# HDMI1.net
KiCad netlist of a schematic drawn in Altium Designer
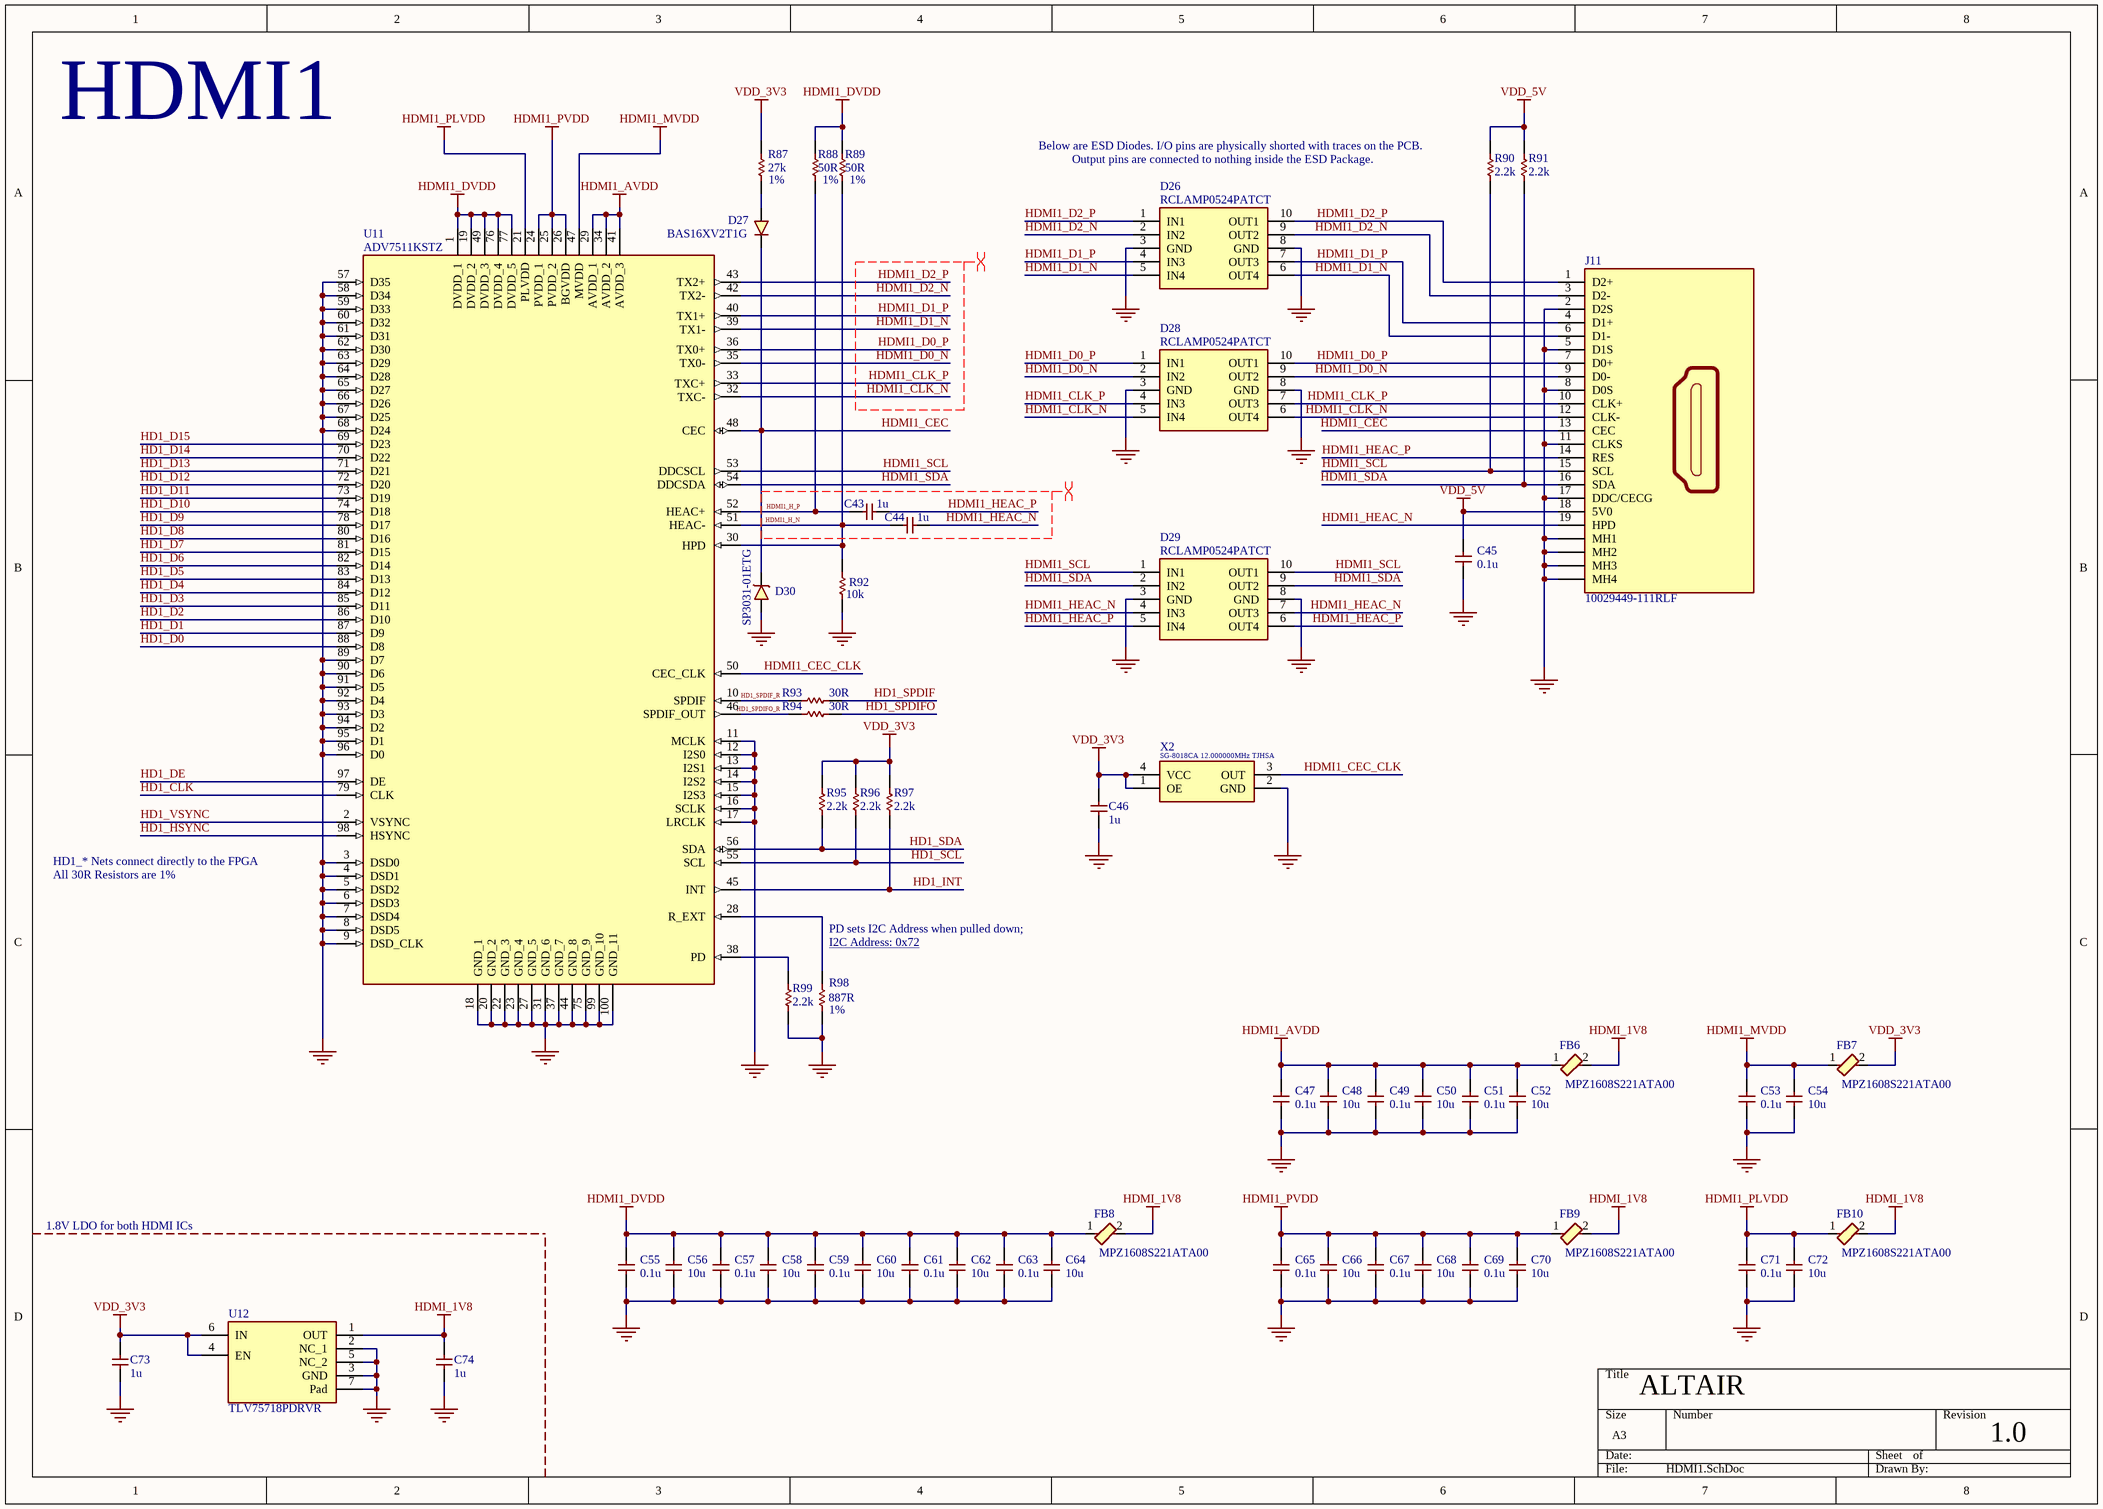
[diagram p0: HDMI1.SchDoc]

(export (version "E")
  (design (tool "Eeschema 10.0.6"))
  (components
    (comp (ref "C43")
      (value "1u")
      (footprint "CAP_0402")
      (description "Capacitor SMD 0402")
      (fields (field (name "JLCPCB PART #") "C14445") (field (name "PART NO") "CL05A105KP5NNNC"))
      (libsource (lib "personalGenericLib") (part "CAP_0402"))
    )
    (comp (ref "C44")
      (value "1u")
      (footprint "CAP_0402")
      (description "Capacitor SMD 0402")
      (fields (field (name "JLCPCB PART #") "C14445") (field (name "PART NO") "CL05A105KP5NNNC"))
      (libsource (lib "personalGenericLib") (part "CAP_0402"))
    )
    (comp (ref "C45")
      (value "0.1u")
      (footprint "CAP_0402")
      (description "Capacitor SMD 0402")
      (fields (field (name "PART NO") "CL05B104KO5NNNC") (field (name "JLCPCB PART #") "C338112"))
      (libsource (lib "personalGenericLib") (part "CAP_0402"))
    )
    (comp (ref "C46")
      (value "1u")
      (footprint "CAP_0402")
      (description "Capacitor SMD 0402")
      (fields (field (name "JLCPCB PART #") "C14445") (field (name "PART NO") "CL05A105KP5NNNC"))
      (libsource (lib "personalGenericLib") (part "CAP_0402"))
    )
    (comp (ref "C47")
      (value "0.1u")
      (footprint "CAP_0402")
      (description "Capacitor SMD 0402")
      (fields (field (name "PART NO") "CL05B104KO5NNNC") (field (name "JLCPCB PART #") "C338112"))
      (libsource (lib "personalGenericLib") (part "CAP_0402"))
    )
    (comp (ref "C48")
      (value "10u")
      (footprint "CAP_0402")
      (description "Capacitor SMD 0402")
      (fields (field (name "JLCPCB PART #") "C315248") (field (name "PART NO") "CL05A106MP5NUNC"))
      (libsource (lib "personalGenericLib") (part "CAP_0402"))
    )
    (comp (ref "C49")
      (value "0.1u")
      (footprint "CAP_0402")
      (description "Capacitor SMD 0402")
      (fields (field (name "PART NO") "CL05B104KO5NNNC") (field (name "JLCPCB PART #") "C338112"))
      (libsource (lib "personalGenericLib") (part "CAP_0402"))
    )
    (comp (ref "C50")
      (value "10u")
      (footprint "CAP_0402")
      (description "Capacitor SMD 0402")
      (fields (field (name "JLCPCB PART #") "C315248") (field (name "PART NO") "CL05A106MP5NUNC"))
      (libsource (lib "personalGenericLib") (part "CAP_0402"))
    )
    (comp (ref "C51")
      (value "0.1u")
      (footprint "CAP_0402")
      (description "Capacitor SMD 0402")
      (fields (field (name "PART NO") "CL05B104KO5NNNC") (field (name "JLCPCB PART #") "C338112"))
      (libsource (lib "personalGenericLib") (part "CAP_0402"))
    )
    (comp (ref "C52")
      (value "10u")
      (footprint "CAP_0402")
      (description "Capacitor SMD 0402")
      (fields (field (name "JLCPCB PART #") "C315248") (field (name "PART NO") "CL05A106MP5NUNC"))
      (libsource (lib "personalGenericLib") (part "CAP_0402"))
    )
    (comp (ref "C53")
      (value "0.1u")
      (footprint "CAP_0402")
      (description "Capacitor SMD 0402")
      (fields (field (name "PART NO") "CL05B104KO5NNNC") (field (name "JLCPCB PART #") "C338112"))
      (libsource (lib "personalGenericLib") (part "CAP_0402"))
    )
    (comp (ref "C54")
      (value "10u")
      (footprint "CAP_0402")
      (description "Capacitor SMD 0402")
      (fields (field (name "JLCPCB PART #") "C315248") (field (name "PART NO") "CL05A106MP5NUNC"))
      (libsource (lib "personalGenericLib") (part "CAP_0402"))
    )
    (comp (ref "C55")
      (value "0.1u")
      (footprint "CAP_0402")
      (description "Capacitor SMD 0402")
      (fields (field (name "PART NO") "CL05B104KO5NNNC") (field (name "JLCPCB PART #") "C338112"))
      (libsource (lib "personalGenericLib") (part "CAP_0402"))
    )
    (comp (ref "C56")
      (value "10u")
      (footprint "CAP_0402")
      (description "Capacitor SMD 0402")
      (fields (field (name "JLCPCB PART #") "C315248") (field (name "PART NO") "CL05A106MP5NUNC"))
      (libsource (lib "personalGenericLib") (part "CAP_0402"))
    )
    (comp (ref "C57")
      (value "0.1u")
      (footprint "CAP_0402")
      (description "Capacitor SMD 0402")
      (fields (field (name "PART NO") "CL05B104KO5NNNC") (field (name "JLCPCB PART #") "C338112"))
      (libsource (lib "personalGenericLib") (part "CAP_0402"))
    )
    (comp (ref "C58")
      (value "10u")
      (footprint "CAP_0402")
      (description "Capacitor SMD 0402")
      (fields (field (name "JLCPCB PART #") "C315248") (field (name "PART NO") "CL05A106MP5NUNC"))
      (libsource (lib "personalGenericLib") (part "CAP_0402"))
    )
    (comp (ref "C59")
      (value "0.1u")
      (footprint "CAP_0402")
      (description "Capacitor SMD 0402")
      (fields (field (name "PART NO") "CL05B104KO5NNNC") (field (name "JLCPCB PART #") "C338112"))
      (libsource (lib "personalGenericLib") (part "CAP_0402"))
    )
    (comp (ref "C60")
      (value "10u")
      (footprint "CAP_0402")
      (description "Capacitor SMD 0402")
      (fields (field (name "JLCPCB PART #") "C315248") (field (name "PART NO") "CL05A106MP5NUNC"))
      (libsource (lib "personalGenericLib") (part "CAP_0402"))
    )
    (comp (ref "C61")
      (value "0.1u")
      (footprint "CAP_0402")
      (description "Capacitor SMD 0402")
      (fields (field (name "PART NO") "CL05B104KO5NNNC") (field (name "JLCPCB PART #") "C338112"))
      (libsource (lib "personalGenericLib") (part "CAP_0402"))
    )
    (comp (ref "C62")
      (value "10u")
      (footprint "CAP_0402")
      (description "Capacitor SMD 0402")
      (fields (field (name "JLCPCB PART #") "C315248") (field (name "PART NO") "CL05A106MP5NUNC"))
      (libsource (lib "personalGenericLib") (part "CAP_0402"))
    )
    (comp (ref "C63")
      (value "0.1u")
      (footprint "CAP_0402")
      (description "Capacitor SMD 0402")
      (fields (field (name "PART NO") "CL05B104KO5NNNC") (field (name "JLCPCB PART #") "C338112"))
      (libsource (lib "personalGenericLib") (part "CAP_0402"))
    )
    (comp (ref "C64")
      (value "10u")
      (footprint "CAP_0402")
      (description "Capacitor SMD 0402")
      (fields (field (name "JLCPCB PART #") "C315248") (field (name "PART NO") "CL05A106MP5NUNC"))
      (libsource (lib "personalGenericLib") (part "CAP_0402"))
    )
    (comp (ref "C65")
      (value "0.1u")
      (footprint "CAP_0402")
      (description "Capacitor SMD 0402")
      (fields (field (name "PART NO") "CL05B104KO5NNNC") (field (name "JLCPCB PART #") "C338112"))
      (libsource (lib "personalGenericLib") (part "CAP_0402"))
    )
    (comp (ref "C66")
      (value "10u")
      (footprint "CAP_0402")
      (description "Capacitor SMD 0402")
      (fields (field (name "JLCPCB PART #") "C315248") (field (name "PART NO") "CL05A106MP5NUNC"))
      (libsource (lib "personalGenericLib") (part "CAP_0402"))
    )
    (comp (ref "C67")
      (value "0.1u")
      (footprint "CAP_0402")
      (description "Capacitor SMD 0402")
      (fields (field (name "PART NO") "CL05B104KO5NNNC") (field (name "JLCPCB PART #") "C338112"))
      (libsource (lib "personalGenericLib") (part "CAP_0402"))
    )
    (comp (ref "C68")
      (value "10u")
      (footprint "CAP_0402")
      (description "Capacitor SMD 0402")
      (fields (field (name "JLCPCB PART #") "C315248") (field (name "PART NO") "CL05A106MP5NUNC"))
      (libsource (lib "personalGenericLib") (part "CAP_0402"))
    )
    (comp (ref "C69")
      (value "0.1u")
      (footprint "CAP_0402")
      (description "Capacitor SMD 0402")
      (fields (field (name "PART NO") "CL05B104KO5NNNC") (field (name "JLCPCB PART #") "C338112"))
      (libsource (lib "personalGenericLib") (part "CAP_0402"))
    )
    (comp (ref "C70")
      (value "10u")
      (footprint "CAP_0402")
      (description "Capacitor SMD 0402")
      (fields (field (name "JLCPCB PART #") "C315248") (field (name "PART NO") "CL05A106MP5NUNC"))
      (libsource (lib "personalGenericLib") (part "CAP_0402"))
    )
    (comp (ref "C71")
      (value "0.1u")
      (footprint "CAP_0402")
      (description "Capacitor SMD 0402")
      (fields (field (name "PART NO") "CL05B104KO5NNNC") (field (name "JLCPCB PART #") "C338112"))
      (libsource (lib "personalGenericLib") (part "CAP_0402"))
    )
    (comp (ref "C72")
      (value "10u")
      (footprint "CAP_0402")
      (description "Capacitor SMD 0402")
      (fields (field (name "JLCPCB PART #") "C315248") (field (name "PART NO") "CL05A106MP5NUNC"))
      (libsource (lib "personalGenericLib") (part "CAP_0402"))
    )
    (comp (ref "C73")
      (value "1u")
      (footprint "CAP_0402")
      (description "Capacitor SMD 0402")
      (fields (field (name "JLCPCB PART #") "C14445") (field (name "PART NO") "CL05A105KP5NNNC"))
      (libsource (lib "personalGenericLib") (part "CAP_0402"))
    )
    (comp (ref "C74")
      (value "1u")
      (footprint "CAP_0402")
      (description "Capacitor SMD 0402")
      (fields (field (name "JLCPCB PART #") "C14445") (field (name "PART NO") "CL05A105KP5NNNC"))
      (libsource (lib "personalGenericLib") (part "CAP_0402"))
    )
    (comp (ref "D26")
      (value "RCLAMP0524PATCT")
      (footprint "RCLAMP0524PATCT")
      (description "TVS Diode (Uni-directional)")
      (fields (field (name "JLCPCB PART #") "C40960"))
      (libsource (lib "personalGenericLib") (part "RCLAMP0524PATCT"))
    )
    (comp (ref "D27")
      (value "BAS16XV2T1G")
      (footprint "SODFL1608X70N")
      (description "Diode (Switching)")
      (fields (field (name "JLCPCB PART #") "C152479"))
      (libsource (lib "personalGenericLib") (part "BAS16XV2T1G"))
    )
    (comp (ref "D28")
      (value "RCLAMP0524PATCT")
      (footprint "RCLAMP0524PATCT")
      (description "TVS Diode (Uni-directional)")
      (fields (field (name "JLCPCB PART #") "C40960"))
      (libsource (lib "personalGenericLib") (part "RCLAMP0524PATCT"))
    )
    (comp (ref "D29")
      (value "RCLAMP0524PATCT")
      (footprint "RCLAMP0524PATCT")
      (description "TVS Diode (Uni-directional)")
      (fields (field (name "JLCPCB PART #") "C40960"))
      (libsource (lib "personalGenericLib") (part "RCLAMP0524PATCT"))
    )
    (comp (ref "D30")
      (value "SP3031-01ETG")
      (footprint "SP303101ETG")
      (description "TVS Diode (Uni-directional)")
      (fields (field (name "JLCPCB PART #") "C207283"))
      (libsource (lib "personalGenericLib") (part "SP3031-01ETG"))
    )
    (comp (ref "FB6")
      (value "220")
      (footprint "BEADC1608X75N")
      (description "Ferrite Bead")
      (fields (field (name "PART NO") "MPZ1608S221ATA00") (field (name "JLCPCB PART #") "C76815"))
      (libsource (lib "personalGenericLib") (part "MPZ1608S221ATA00"))
    )
    (comp (ref "FB7")
      (value "220")
      (footprint "BEADC1608X75N")
      (description "Ferrite Bead")
      (fields (field (name "PART NO") "MPZ1608S221ATA00") (field (name "JLCPCB PART #") "C76815"))
      (libsource (lib "personalGenericLib") (part "MPZ1608S221ATA00"))
    )
    (comp (ref "FB8")
      (value "220")
      (footprint "BEADC1608X75N")
      (description "Ferrite Bead")
      (fields (field (name "PART NO") "MPZ1608S221ATA00") (field (name "JLCPCB PART #") "C76815"))
      (libsource (lib "personalGenericLib") (part "MPZ1608S221ATA00"))
    )
    (comp (ref "FB9")
      (value "220")
      (footprint "BEADC1608X75N")
      (description "Ferrite Bead")
      (fields (field (name "PART NO") "MPZ1608S221ATA00") (field (name "JLCPCB PART #") "C76815"))
      (libsource (lib "personalGenericLib") (part "MPZ1608S221ATA00"))
    )
    (comp (ref "FB10")
      (value "220")
      (footprint "BEADC1608X75N")
      (description "Ferrite Bead")
      (fields (field (name "PART NO") "MPZ1608S221ATA00") (field (name "JLCPCB PART #") "C76815"))
      (libsource (lib "personalGenericLib") (part "MPZ1608S221ATA00"))
    )
    (comp (ref "J11")
      (value "10029449-111RLF")
      (footprint "10029449111RLF")
      (description "HDMI Connector")
      (fields (field (name "JLCPCB PART #") "C427307"))
      (libsource (lib "personalGenericLib") (part "10029449-111RLF"))
    )
    (comp (ref "R87")
      (value "27k")
      (footprint "RES_0402")
      (description "Resistor SMD 0402")
      (fields
        (field (name "JLCPCB PART #") "C138022")
        (field (name "NOTE/MISC") "1%")
        (field (name "PART NO") "RC0402FR-0727KL")
      )
      (libsource (lib "personalGenericLib") (part "RES_0402"))
    )
    (comp (ref "R88")
      (value "50R")
      (footprint "RES_0402")
      (description "Resistor SMD 0402")
      (fields
        (field (name "JLCPCB PART #") "C853312")
        (field (name "NOTE/MISC") "1%")
        (field (name "PART NO") "RT0402BRE0750RL")
      )
      (libsource (lib "personalGenericLib") (part "RES_0402"))
    )
    (comp (ref "R89")
      (value "50R")
      (footprint "RES_0402")
      (description "Resistor SMD 0402")
      (fields
        (field (name "JLCPCB PART #") "C853312")
        (field (name "NOTE/MISC") "1%")
        (field (name "PART NO") "RT0402BRE0750RL")
      )
      (libsource (lib "personalGenericLib") (part "RES_0402"))
    )
    (comp (ref "R90")
      (value "2.2k")
      (footprint "RES_0402")
      (description "Resistor SMD 0402")
      (fields (field (name "JLCPCB PART #") "C163447") (field (name "PART NO") "RC0402JR-072K2L"))
      (libsource (lib "personalGenericLib") (part "RES_0402"))
    )
    (comp (ref "R91")
      (value "2.2k")
      (footprint "RES_0402")
      (description "Resistor SMD 0402")
      (fields (field (name "JLCPCB PART #") "C163447") (field (name "PART NO") "RC0402JR-072K2L"))
      (libsource (lib "personalGenericLib") (part "RES_0402"))
    )
    (comp (ref "R92")
      (value "10k")
      (footprint "RES_0402")
      (description "Resistor SMD 0402")
      (fields (field (name "JLCPCB PART #") "C60489") (field (name "PART NO") "RC0402JR-0710KL"))
      (libsource (lib "personalGenericLib") (part "RES_0402"))
    )
    (comp (ref "R93")
      (value "30R")
      (footprint "RES_0402")
      (description "Resistor SMD 0402")
      (fields (field (name "JLCPCB PART #") "C138007") (field (name "PART NO") "RC0402FR-0730RL"))
      (libsource (lib "personalGenericLib") (part "RES_0402"))
    )
    (comp (ref "R94")
      (value "30R")
      (footprint "RES_0402")
      (description "Resistor SMD 0402")
      (fields (field (name "JLCPCB PART #") "C138007") (field (name "PART NO") "RC0402FR-0730RL"))
      (libsource (lib "personalGenericLib") (part "RES_0402"))
    )
    (comp (ref "R95")
      (value "2.2k")
      (footprint "RES_0402")
      (description "Resistor SMD 0402")
      (fields (field (name "JLCPCB PART #") "C163447") (field (name "PART NO") "RC0402JR-072K2L"))
      (libsource (lib "personalGenericLib") (part "RES_0402"))
    )
    (comp (ref "R96")
      (value "2.2k")
      (footprint "RES_0402")
      (description "Resistor SMD 0402")
      (fields (field (name "JLCPCB PART #") "C163447") (field (name "PART NO") "RC0402JR-072K2L"))
      (libsource (lib "personalGenericLib") (part "RES_0402"))
    )
    (comp (ref "R97")
      (value "2.2k")
      (footprint "RES_0402")
      (description "Resistor SMD 0402")
      (fields (field (name "JLCPCB PART #") "C163447") (field (name "PART NO") "RC0402JR-072K2L"))
      (libsource (lib "personalGenericLib") (part "RES_0402"))
    )
    (comp (ref "R98")
      (value "887R")
      (footprint "RES_0402")
      (description "Resistor SMD 0402")
      (fields
        (field (name "JLCPCB PART #") "C4012675")
        (field (name "NOTE/MISC") "1%")
        (field (name "PART NO") "CRCW0402887RFKED")
      )
      (libsource (lib "personalGenericLib") (part "RES_0402"))
    )
    (comp (ref "R99")
      (value "2.2k")
      (footprint "RES_0402")
      (description "Resistor SMD 0402")
      (fields (field (name "JLCPCB PART #") "C163447") (field (name "PART NO") "RC0402JR-072K2L"))
      (libsource (lib "personalGenericLib") (part "RES_0402"))
    )
    (comp (ref "U11")
      (value "ADV7511KSTZ")
      (footprint "QFP50P1600X1600X160-100N")
      (description "HDMI RX IC")
      (fields (field (name "JLCPCB PART #") "C179459"))
      (libsource (lib "personalGenericLib") (part "ADV7511KSTZ"))
    )
    (comp (ref "U12")
      (value "TLV75718PDRVR")
      (footprint "SON65P200X200X80-7N")
      (description "LDO 1V8, 1V45-5V5 Input")
      (fields (field (name "JLCPCB PART #") "C2861386"))
      (libsource (lib "personalGenericLib") (part "TLV75718PDRVR"))
    )
    (comp (ref "X2")
      (value "SG-8018CA 12.000000MHz TJHSA")
      (footprint "SG8018CA147456MTJHPA3")
      (description "12 MHz Programmable Oscillator")
      (fields (field (name "JLCPCB PART #") "C390417"))
      (libsource (lib "personalGenericLib") (part "SG-8018CA 12.000000MHz TJHSA"))
    )
  )
  (nets
    (net (code "1") (name "/HD1_CLK") (class "Default")
      (node (ref "U11") (pin "79") (pinfunction "CLK_79") (pintype "input"))
    )
    (net (code "2") (name "/HD1_D0") (class "Default")
      (node (ref "U11") (pin "88") (pinfunction "D8_88") (pintype "input"))
    )
    (net (code "3") (name "/HD1_D1") (class "Default")
      (node (ref "U11") (pin "87") (pinfunction "D9_87") (pintype "input"))
    )
    (net (code "4") (name "/HD1_D2") (class "Default")
      (node (ref "U11") (pin "86") (pinfunction "D10_86") (pintype "input"))
    )
    (net (code "5") (name "/HD1_D3") (class "Default")
      (node (ref "U11") (pin "85") (pinfunction "D11_85") (pintype "input"))
    )
    (net (code "6") (name "/HD1_D4") (class "Default")
      (node (ref "U11") (pin "84") (pinfunction "D12_84") (pintype "input"))
    )
    (net (code "7") (name "/HD1_D5") (class "Default")
      (node (ref "U11") (pin "83") (pinfunction "D13_83") (pintype "input"))
    )
    (net (code "8") (name "/HD1_D6") (class "Default")
      (node (ref "U11") (pin "82") (pinfunction "D14_82") (pintype "input"))
    )
    (net (code "9") (name "/HD1_D7") (class "Default")
      (node (ref "U11") (pin "81") (pinfunction "D15_81") (pintype "input"))
    )
    (net (code "10") (name "/HD1_D8") (class "Default")
      (node (ref "U11") (pin "80") (pinfunction "D16_80") (pintype "input"))
    )
    (net (code "11") (name "/HD1_D9") (class "Default")
      (node (ref "U11") (pin "78") (pinfunction "D17_78") (pintype "input"))
    )
    (net (code "12") (name "/HD1_D10") (class "Default")
      (node (ref "U11") (pin "74") (pinfunction "D18_74") (pintype "input"))
    )
    (net (code "13") (name "/HD1_D11") (class "Default")
      (node (ref "U11") (pin "73") (pinfunction "D19_73") (pintype "input"))
    )
    (net (code "14") (name "/HD1_D12") (class "Default")
      (node (ref "U11") (pin "72") (pinfunction "D20_72") (pintype "input"))
    )
    (net (code "15") (name "/HD1_D13") (class "Default")
      (node (ref "U11") (pin "71") (pinfunction "D21_71") (pintype "input"))
    )
    (net (code "16") (name "/HD1_D14") (class "Default")
      (node (ref "U11") (pin "70") (pinfunction "D22_70") (pintype "input"))
    )
    (net (code "17") (name "/HD1_D15") (class "Default")
      (node (ref "U11") (pin "69") (pinfunction "D23_69") (pintype "input"))
    )
    (net (code "18") (name "/HD1_DE") (class "Default")
      (node (ref "U11") (pin "97") (pinfunction "DE_97") (pintype "input"))
    )
    (net (code "19") (name "/HD1_HSYNC") (class "Default")
      (node (ref "U11") (pin "98") (pinfunction "HSYNC_98") (pintype "input"))
    )
    (net (code "20") (name "/HD1_INT") (class "Default")
      (node (ref "R97") (pin "1") (pinfunction "1_1") (pintype "passive"))
      (node (ref "U11") (pin "45") (pinfunction "INT_45") (pintype "output"))
    )
    (net (code "21") (name "/HD1_SCL") (class "Default")
      (node (ref "R96") (pin "1") (pinfunction "1_1") (pintype "passive"))
      (node (ref "U11") (pin "55") (pinfunction "SCL_55") (pintype "input"))
    )
    (net (code "22") (name "/HD1_SDA") (class "Default")
      (node (ref "R95") (pin "1") (pinfunction "1_1") (pintype "passive"))
      (node (ref "U11") (pin "56") (pinfunction "SDA_56") (pintype "bidirectional"))
    )
    (net (code "23") (name "/HD1_SPDIF") (class "Default")
      (node (ref "R93") (pin "2") (pinfunction "2_2") (pintype "passive"))
    )
    (net (code "24") (name "/HD1_SPDIFO") (class "Default")
      (node (ref "R94") (pin "2") (pinfunction "2_2") (pintype "passive"))
    )
    (net (code "25") (name "/HD1_SPDIFO_R") (class "Default")
      (node (ref "R94") (pin "1") (pinfunction "1_1") (pintype "passive"))
      (node (ref "U11") (pin "46") (pinfunction "SPDIF_OUT_46") (pintype "output"))
    )
    (net (code "26") (name "/HD1_SPDIF_R") (class "Default")
      (node (ref "R93") (pin "1") (pinfunction "1_1") (pintype "passive"))
      (node (ref "U11") (pin "10") (pinfunction "SPDIF_10") (pintype "input"))
    )
    (net (code "27") (name "/HD1_VSYNC") (class "Default")
      (node (ref "U11") (pin "2") (pinfunction "VSYNC_2") (pintype "input"))
    )
    (net (code "28") (name "/HDMI1_CEC") (class "Default")
      (node (ref "D27") (pin "1") (pinfunction "K_1") (pintype "passive"))
      (node (ref "D30") (pin "1") (pinfunction "K_1") (pintype "passive"))
      (node (ref "J11") (pin "13") (pinfunction "CEC_13") (pintype "passive"))
      (node (ref "U11") (pin "48") (pinfunction "CEC_48") (pintype "bidirectional"))
    )
    (net (code "29") (name "/HDMI1_CEC_CLK") (class "Default")
      (node (ref "U11") (pin "50") (pinfunction "CEC_CLK_50") (pintype "input"))
      (node (ref "X2") (pin "3") (pinfunction "OUT_3") (pintype "passive"))
    )
    (net (code "30") (name "/HDMI1_CLK_N") (class "Default")
      (node (ref "D28") (pin "5") (pinfunction "IN4_5") (pintype "passive"))
      (node (ref "D28") (pin "6") (pinfunction "OUT4_6") (pintype "passive"))
      (node (ref "J11") (pin "12") (pinfunction "CLK-_12") (pintype "passive"))
      (node (ref "U11") (pin "32") (pinfunction "TXC-_32") (pintype "output"))
    )
    (net (code "31") (name "/HDMI1_CLK_P") (class "Default")
      (node (ref "D28") (pin "4") (pinfunction "IN3_4") (pintype "passive"))
      (node (ref "D28") (pin "7") (pinfunction "OUT3_7") (pintype "passive"))
      (node (ref "J11") (pin "10") (pinfunction "CLK+_10") (pintype "passive"))
      (node (ref "U11") (pin "33") (pinfunction "TXC+_33") (pintype "output"))
    )
    (net (code "32") (name "/HDMI1_D0_N") (class "Default")
      (node (ref "D28") (pin "2") (pinfunction "IN2_2") (pintype "passive"))
      (node (ref "D28") (pin "9") (pinfunction "OUT2_9") (pintype "passive"))
      (node (ref "J11") (pin "9") (pinfunction "D0-_9") (pintype "passive"))
      (node (ref "U11") (pin "35") (pinfunction "TX0-_35") (pintype "output"))
    )
    (net (code "33") (name "/HDMI1_D0_P") (class "Default")
      (node (ref "D28") (pin "1") (pinfunction "IN1_1") (pintype "passive"))
      (node (ref "D28") (pin "10") (pinfunction "OUT1_10") (pintype "passive"))
      (node (ref "J11") (pin "7") (pinfunction "D0+_7") (pintype "passive"))
      (node (ref "U11") (pin "36") (pinfunction "TX0+_36") (pintype "output"))
    )
    (net (code "34") (name "/HDMI1_D1_N") (class "Default")
      (node (ref "D26") (pin "5") (pinfunction "IN4_5") (pintype "passive"))
      (node (ref "D26") (pin "6") (pinfunction "OUT4_6") (pintype "passive"))
      (node (ref "J11") (pin "6") (pinfunction "D1-_6") (pintype "passive"))
      (node (ref "U11") (pin "39") (pinfunction "TX1-_39") (pintype "output"))
    )
    (net (code "35") (name "/HDMI1_D1_P") (class "Default")
      (node (ref "D26") (pin "4") (pinfunction "IN3_4") (pintype "passive"))
      (node (ref "D26") (pin "7") (pinfunction "OUT3_7") (pintype "passive"))
      (node (ref "J11") (pin "4") (pinfunction "D1+_4") (pintype "passive"))
      (node (ref "U11") (pin "40") (pinfunction "TX1+_40") (pintype "output"))
    )
    (net (code "36") (name "/HDMI1_D2_N") (class "Default")
      (node (ref "D26") (pin "2") (pinfunction "IN2_2") (pintype "passive"))
      (node (ref "D26") (pin "9") (pinfunction "OUT2_9") (pintype "passive"))
      (node (ref "J11") (pin "3") (pinfunction "D2-_3") (pintype "passive"))
      (node (ref "U11") (pin "42") (pinfunction "TX2-_42") (pintype "output"))
    )
    (net (code "37") (name "/HDMI1_D2_P") (class "Default")
      (node (ref "D26") (pin "1") (pinfunction "IN1_1") (pintype "passive"))
      (node (ref "D26") (pin "10") (pinfunction "OUT1_10") (pintype "passive"))
      (node (ref "J11") (pin "1") (pinfunction "D2+_1") (pintype "passive"))
      (node (ref "U11") (pin "43") (pinfunction "TX2+_43") (pintype "output"))
    )
    (net (code "38") (name "/HDMI1_HEAC_N") (class "Default")
      (node (ref "C44") (pin "1") (pinfunction "1_1") (pintype "passive"))
      (node (ref "D29") (pin "4") (pinfunction "IN3_4") (pintype "passive"))
      (node (ref "D29") (pin "7") (pinfunction "OUT3_7") (pintype "passive"))
      (node (ref "J11") (pin "19") (pinfunction "HPD_19") (pintype "passive"))
    )
    (net (code "39") (name "/HDMI1_HEAC_P") (class "Default")
      (node (ref "C43") (pin "1") (pinfunction "1_1") (pintype "passive"))
      (node (ref "D29") (pin "5") (pinfunction "IN4_5") (pintype "passive"))
      (node (ref "D29") (pin "6") (pinfunction "OUT4_6") (pintype "passive"))
      (node (ref "J11") (pin "14") (pinfunction "RES_14") (pintype "passive"))
    )
    (net (code "40") (name "/HDMI1_H_N") (class "Default")
      (node (ref "C44") (pin "2") (pinfunction "2_2") (pintype "passive"))
      (node (ref "R89") (pin "2") (pinfunction "2_2") (pintype "passive"))
      (node (ref "R92") (pin "1") (pinfunction "1_1") (pintype "passive"))
      (node (ref "U11") (pin "30") (pinfunction "HPD_30") (pintype "input"))
      (node (ref "U11") (pin "51") (pinfunction "HEAC-_51") (pintype "input"))
    )
    (net (code "41") (name "/HDMI1_H_P") (class "Default")
      (node (ref "C43") (pin "2") (pinfunction "2_2") (pintype "passive"))
      (node (ref "R88") (pin "2") (pinfunction "2_2") (pintype "passive"))
      (node (ref "U11") (pin "52") (pinfunction "HEAC+_52") (pintype "input"))
    )
    (net (code "42") (name "/HDMI1_SCL") (class "Default")
      (node (ref "D29") (pin "1") (pinfunction "IN1_1") (pintype "passive"))
      (node (ref "D29") (pin "10") (pinfunction "OUT1_10") (pintype "passive"))
      (node (ref "J11") (pin "15") (pinfunction "SCL_15") (pintype "passive"))
      (node (ref "R90") (pin "1") (pinfunction "1_1") (pintype "passive"))
      (node (ref "U11") (pin "53") (pinfunction "DDCSCL_53") (pintype "output"))
    )
    (net (code "43") (name "/HDMI1_SDA") (class "Default")
      (node (ref "D29") (pin "2") (pinfunction "IN2_2") (pintype "passive"))
      (node (ref "D29") (pin "9") (pinfunction "OUT2_9") (pintype "passive"))
      (node (ref "J11") (pin "16") (pinfunction "SDA_16") (pintype "passive"))
      (node (ref "R91") (pin "1") (pinfunction "1_1") (pintype "passive"))
      (node (ref "U11") (pin "54") (pinfunction "DDCSDA_54") (pintype "bidirectional"))
    )
    (net (code "44") (name "GND") (class "Default")
      (node (ref "C45") (pin "1") (pinfunction "1_1") (pintype "passive"))
      (node (ref "C46") (pin "2") (pinfunction "2_2") (pintype "passive"))
      (node (ref "C47") (pin "1") (pinfunction "1_1") (pintype "passive"))
      (node (ref "C48") (pin "2") (pinfunction "2_2") (pintype "passive"))
      (node (ref "C49") (pin "1") (pinfunction "1_1") (pintype "passive"))
      (node (ref "C50") (pin "2") (pinfunction "2_2") (pintype "passive"))
      (node (ref "C51") (pin "1") (pinfunction "1_1") (pintype "passive"))
      (node (ref "C52") (pin "2") (pinfunction "2_2") (pintype "passive"))
      (node (ref "C53") (pin "1") (pinfunction "1_1") (pintype "passive"))
      (node (ref "C54") (pin "2") (pinfunction "2_2") (pintype "passive"))
      (node (ref "C55") (pin "1") (pinfunction "1_1") (pintype "passive"))
      (node (ref "C56") (pin "2") (pinfunction "2_2") (pintype "passive"))
      (node (ref "C57") (pin "1") (pinfunction "1_1") (pintype "passive"))
      (node (ref "C58") (pin "2") (pinfunction "2_2") (pintype "passive"))
      (node (ref "C59") (pin "1") (pinfunction "1_1") (pintype "passive"))
      (node (ref "C60") (pin "2") (pinfunction "2_2") (pintype "passive"))
      (node (ref "C61") (pin "1") (pinfunction "1_1") (pintype "passive"))
      (node (ref "C62") (pin "2") (pinfunction "2_2") (pintype "passive"))
      (node (ref "C63") (pin "1") (pinfunction "1_1") (pintype "passive"))
      (node (ref "C64") (pin "2") (pinfunction "2_2") (pintype "passive"))
      (node (ref "C65") (pin "1") (pinfunction "1_1") (pintype "passive"))
      (node (ref "C66") (pin "2") (pinfunction "2_2") (pintype "passive"))
      (node (ref "C67") (pin "1") (pinfunction "1_1") (pintype "passive"))
      (node (ref "C68") (pin "2") (pinfunction "2_2") (pintype "passive"))
      (node (ref "C69") (pin "1") (pinfunction "1_1") (pintype "passive"))
      (node (ref "C70") (pin "2") (pinfunction "2_2") (pintype "passive"))
      (node (ref "C71") (pin "1") (pinfunction "1_1") (pintype "passive"))
      (node (ref "C72") (pin "2") (pinfunction "2_2") (pintype "passive"))
      (node (ref "C73") (pin "2") (pinfunction "2_2") (pintype "passive"))
      (node (ref "C74") (pin "2") (pinfunction "2_2") (pintype "passive"))
      (node (ref "D26") (pin "3") (pinfunction "GND_3") (pintype "passive"))
      (node (ref "D26") (pin "8") (pinfunction "GND_8") (pintype "passive"))
      (node (ref "D28") (pin "3") (pinfunction "GND_3") (pintype "passive"))
      (node (ref "D28") (pin "8") (pinfunction "GND_8") (pintype "passive"))
      (node (ref "D29") (pin "3") (pinfunction "GND_3") (pintype "passive"))
      (node (ref "D29") (pin "8") (pinfunction "GND_8") (pintype "passive"))
      (node (ref "D30") (pin "2") (pinfunction "A_2") (pintype "passive"))
      (node (ref "J11") (pin "11") (pinfunction "CLKS_11") (pintype "passive"))
      (node (ref "J11") (pin "17") (pinfunction "DDC/CECG_17") (pintype "passive"))
      (node (ref "J11") (pin "2") (pinfunction "D2S_2") (pintype "passive"))
      (node (ref "J11") (pin "5") (pinfunction "D1S_5") (pintype "passive"))
      (node (ref "J11") (pin "8") (pinfunction "D0S_8") (pintype "passive"))
      (node (ref "J11") (pin "MH1") (pinfunction "MH1_MH1") (pintype "passive"))
      (node (ref "J11") (pin "MH2") (pinfunction "MH2_MH2") (pintype "passive"))
      (node (ref "J11") (pin "MH3") (pinfunction "MH3_MH3") (pintype "passive"))
      (node (ref "J11") (pin "MH4") (pinfunction "MH4_MH4") (pintype "passive"))
      (node (ref "R92") (pin "2") (pinfunction "2_2") (pintype "passive"))
      (node (ref "R98") (pin "2") (pinfunction "2_2") (pintype "passive"))
      (node (ref "R99") (pin "1") (pinfunction "1_1") (pintype "passive"))
      (node (ref "U11") (pin "100") (pinfunction "GND_11_100") (pintype "power_in"))
      (node (ref "U11") (pin "11") (pinfunction "MCLK_11") (pintype "input"))
      (node (ref "U11") (pin "12") (pinfunction "I2S0_12") (pintype "input"))
      (node (ref "U11") (pin "13") (pinfunction "I2S1_13") (pintype "input"))
      (node (ref "U11") (pin "14") (pinfunction "I2S2_14") (pintype "input"))
      (node (ref "U11") (pin "15") (pinfunction "I2S3_15") (pintype "input"))
      (node (ref "U11") (pin "16") (pinfunction "SCLK_16") (pintype "input"))
      (node (ref "U11") (pin "17") (pinfunction "LRCLK_17") (pintype "input"))
      (node (ref "U11") (pin "18") (pinfunction "GND_1_18") (pintype "power_in"))
      (node (ref "U11") (pin "20") (pinfunction "GND_2_20") (pintype "power_in"))
      (node (ref "U11") (pin "22") (pinfunction "GND_3_22") (pintype "power_in"))
      (node (ref "U11") (pin "23") (pinfunction "GND_4_23") (pintype "power_in"))
      (node (ref "U11") (pin "27") (pinfunction "GND_5_27") (pintype "power_in"))
      (node (ref "U11") (pin "3") (pinfunction "DSD0_3") (pintype "input"))
      (node (ref "U11") (pin "31") (pinfunction "GND_6_31") (pintype "power_in"))
      (node (ref "U11") (pin "37") (pinfunction "GND_7_37") (pintype "power_in"))
      (node (ref "U11") (pin "4") (pinfunction "DSD1_4") (pintype "input"))
      (node (ref "U11") (pin "44") (pinfunction "GND_8_44") (pintype "power_in"))
      (node (ref "U11") (pin "5") (pinfunction "DSD2_5") (pintype "input"))
      (node (ref "U11") (pin "57") (pinfunction "D35_57") (pintype "input"))
      (node (ref "U11") (pin "58") (pinfunction "D34_58") (pintype "input"))
      (node (ref "U11") (pin "59") (pinfunction "D33_59") (pintype "input"))
      (node (ref "U11") (pin "6") (pinfunction "DSD3_6") (pintype "input"))
      (node (ref "U11") (pin "60") (pinfunction "D32_60") (pintype "input"))
      (node (ref "U11") (pin "61") (pinfunction "D31_61") (pintype "input"))
      (node (ref "U11") (pin "62") (pinfunction "D30_62") (pintype "input"))
      (node (ref "U11") (pin "63") (pinfunction "D29_63") (pintype "input"))
      (node (ref "U11") (pin "64") (pinfunction "D28_64") (pintype "input"))
      (node (ref "U11") (pin "65") (pinfunction "D27_65") (pintype "input"))
      (node (ref "U11") (pin "66") (pinfunction "D26_66") (pintype "input"))
      (node (ref "U11") (pin "67") (pinfunction "D25_67") (pintype "input"))
      (node (ref "U11") (pin "68") (pinfunction "D24_68") (pintype "input"))
      (node (ref "U11") (pin "7") (pinfunction "DSD4_7") (pintype "input"))
      (node (ref "U11") (pin "75") (pinfunction "GND_9_75") (pintype "power_in"))
      (node (ref "U11") (pin "8") (pinfunction "DSD5_8") (pintype "input"))
      (node (ref "U11") (pin "89") (pinfunction "D7_89") (pintype "input"))
      (node (ref "U11") (pin "9") (pinfunction "DSD_CLK_9") (pintype "input"))
      (node (ref "U11") (pin "90") (pinfunction "D6_90") (pintype "input"))
      (node (ref "U11") (pin "91") (pinfunction "D5_91") (pintype "input"))
      (node (ref "U11") (pin "92") (pinfunction "D4_92") (pintype "input"))
      (node (ref "U11") (pin "93") (pinfunction "D3_93") (pintype "input"))
      (node (ref "U11") (pin "94") (pinfunction "D2_94") (pintype "input"))
      (node (ref "U11") (pin "95") (pinfunction "D1_95") (pintype "input"))
      (node (ref "U11") (pin "96") (pinfunction "D0_96") (pintype "input"))
      (node (ref "U11") (pin "99") (pinfunction "GND_10_99") (pintype "power_in"))
      (node (ref "U12") (pin "2") (pinfunction "NC_1_2") (pintype "passive"))
      (node (ref "U12") (pin "3") (pinfunction "GND_3") (pintype "passive"))
      (node (ref "U12") (pin "5") (pinfunction "NC_2_5") (pintype "passive"))
      (node (ref "U12") (pin "7") (pinfunction "Pad_7") (pintype "passive"))
      (node (ref "X2") (pin "2") (pinfunction "GND_2") (pintype "passive"))
    )
    (net (code "45") (name "HDMI1_AVDD") (class "Default")
      (node (ref "C47") (pin "2") (pinfunction "2_2") (pintype "passive"))
      (node (ref "C48") (pin "1") (pinfunction "1_1") (pintype "passive"))
      (node (ref "C49") (pin "2") (pinfunction "2_2") (pintype "passive"))
      (node (ref "C50") (pin "1") (pinfunction "1_1") (pintype "passive"))
      (node (ref "C51") (pin "2") (pinfunction "2_2") (pintype "passive"))
      (node (ref "C52") (pin "1") (pinfunction "1_1") (pintype "passive"))
      (node (ref "FB6") (pin "1") (pinfunction "1_1") (pintype "passive"))
      (node (ref "U11") (pin "29") (pinfunction "AVDD_1_29") (pintype "power_in"))
      (node (ref "U11") (pin "34") (pinfunction "AVDD_2_34") (pintype "power_in"))
      (node (ref "U11") (pin "41") (pinfunction "AVDD_3_41") (pintype "power_in"))
    )
    (net (code "46") (name "HDMI1_DVDD") (class "Default")
      (node (ref "C55") (pin "2") (pinfunction "2_2") (pintype "passive"))
      (node (ref "C56") (pin "1") (pinfunction "1_1") (pintype "passive"))
      (node (ref "C57") (pin "2") (pinfunction "2_2") (pintype "passive"))
      (node (ref "C58") (pin "1") (pinfunction "1_1") (pintype "passive"))
      (node (ref "C59") (pin "2") (pinfunction "2_2") (pintype "passive"))
      (node (ref "C60") (pin "1") (pinfunction "1_1") (pintype "passive"))
      (node (ref "C61") (pin "2") (pinfunction "2_2") (pintype "passive"))
      (node (ref "C62") (pin "1") (pinfunction "1_1") (pintype "passive"))
      (node (ref "C63") (pin "2") (pinfunction "2_2") (pintype "passive"))
      (node (ref "C64") (pin "1") (pinfunction "1_1") (pintype "passive"))
      (node (ref "FB8") (pin "1") (pinfunction "1_1") (pintype "passive"))
      (node (ref "R88") (pin "1") (pinfunction "1_1") (pintype "passive"))
      (node (ref "R89") (pin "1") (pinfunction "1_1") (pintype "passive"))
      (node (ref "U11") (pin "1") (pinfunction "DVDD_1_1") (pintype "power_in"))
      (node (ref "U11") (pin "19") (pinfunction "DVDD_2_19") (pintype "power_in"))
      (node (ref "U11") (pin "49") (pinfunction "DVDD_3_49") (pintype "power_in"))
      (node (ref "U11") (pin "76") (pinfunction "DVDD_4_76") (pintype "power_in"))
      (node (ref "U11") (pin "77") (pinfunction "DVDD_5_77") (pintype "power_in"))
    )
    (net (code "47") (name "HDMI1_MVDD") (class "Default")
      (node (ref "C53") (pin "2") (pinfunction "2_2") (pintype "passive"))
      (node (ref "C54") (pin "1") (pinfunction "1_1") (pintype "passive"))
      (node (ref "FB7") (pin "1") (pinfunction "1_1") (pintype "passive"))
      (node (ref "U11") (pin "47") (pinfunction "MVDD_47") (pintype "power_in"))
    )
    (net (code "48") (name "HDMI1_PLVDD") (class "Default")
      (node (ref "C71") (pin "2") (pinfunction "2_2") (pintype "passive"))
      (node (ref "C72") (pin "1") (pinfunction "1_1") (pintype "passive"))
      (node (ref "FB10") (pin "1") (pinfunction "1_1") (pintype "passive"))
      (node (ref "U11") (pin "21") (pinfunction "PLVDD_21") (pintype "power_in"))
    )
    (net (code "49") (name "HDMI1_PVDD") (class "Default")
      (node (ref "C65") (pin "2") (pinfunction "2_2") (pintype "passive"))
      (node (ref "C66") (pin "1") (pinfunction "1_1") (pintype "passive"))
      (node (ref "C67") (pin "2") (pinfunction "2_2") (pintype "passive"))
      (node (ref "C68") (pin "1") (pinfunction "1_1") (pintype "passive"))
      (node (ref "C69") (pin "2") (pinfunction "2_2") (pintype "passive"))
      (node (ref "C70") (pin "1") (pinfunction "1_1") (pintype "passive"))
      (node (ref "FB9") (pin "1") (pinfunction "1_1") (pintype "passive"))
      (node (ref "U11") (pin "24") (pinfunction "PVDD_1_24") (pintype "power_in"))
      (node (ref "U11") (pin "25") (pinfunction "PVDD_2_25") (pintype "power_in"))
      (node (ref "U11") (pin "26") (pinfunction "BGVDD_26") (pintype "power_in"))
    )
    (net (code "50") (name "HDMI_1V8") (class "Default")
      (node (ref "C74") (pin "1") (pinfunction "1_1") (pintype "passive"))
      (node (ref "FB10") (pin "2") (pinfunction "2_2") (pintype "passive"))
      (node (ref "FB6") (pin "2") (pinfunction "2_2") (pintype "passive"))
      (node (ref "FB8") (pin "2") (pinfunction "2_2") (pintype "passive"))
      (node (ref "FB9") (pin "2") (pinfunction "2_2") (pintype "passive"))
      (node (ref "U12") (pin "1") (pinfunction "OUT_1") (pintype "passive"))
    )
    (net (code "51") (name "Net-(D27-A)") (class "Default")
      (node (ref "D27") (pin "2") (pinfunction "A_2") (pintype "passive"))
      (node (ref "R87") (pin "2") (pinfunction "2_2") (pintype "passive"))
    )
    (net (code "52") (name "Net-(U11-PD)") (class "Default")
      (node (ref "R99") (pin "2") (pinfunction "2_2") (pintype "passive"))
      (node (ref "U11") (pin "38") (pinfunction "PD_38") (pintype "input"))
    )
    (net (code "53") (name "Net-(U11-R_EXT)") (class "Default")
      (node (ref "R98") (pin "1") (pinfunction "1_1") (pintype "passive"))
      (node (ref "U11") (pin "28") (pinfunction "R_EXT_28") (pintype "input"))
    )
    (net (code "54") (name "VDD_3V3") (class "Default")
      (node (ref "C46") (pin "1") (pinfunction "1_1") (pintype "passive"))
      (node (ref "C73") (pin "1") (pinfunction "1_1") (pintype "passive"))
      (node (ref "FB7") (pin "2") (pinfunction "2_2") (pintype "passive"))
      (node (ref "R87") (pin "1") (pinfunction "1_1") (pintype "passive"))
      (node (ref "R95") (pin "2") (pinfunction "2_2") (pintype "passive"))
      (node (ref "R96") (pin "2") (pinfunction "2_2") (pintype "passive"))
      (node (ref "R97") (pin "2") (pinfunction "2_2") (pintype "passive"))
      (node (ref "U12") (pin "4") (pinfunction "EN_4") (pintype "passive"))
      (node (ref "U12") (pin "6") (pinfunction "IN_6") (pintype "passive"))
      (node (ref "X2") (pin "1") (pinfunction "OE_1") (pintype "passive"))
      (node (ref "X2") (pin "4") (pinfunction "VCC_4") (pintype "passive"))
    )
    (net (code "55") (name "VDD_5V") (class "Default")
      (node (ref "C45") (pin "2") (pinfunction "2_2") (pintype "passive"))
      (node (ref "J11") (pin "18") (pinfunction "5V0_18") (pintype "passive"))
      (node (ref "R90") (pin "2") (pinfunction "2_2") (pintype "passive"))
      (node (ref "R91") (pin "2") (pinfunction "2_2") (pintype "passive"))
    )
  )
)
